# schematic.net
KiCad netlist of a schematic drawn in Altium Designer
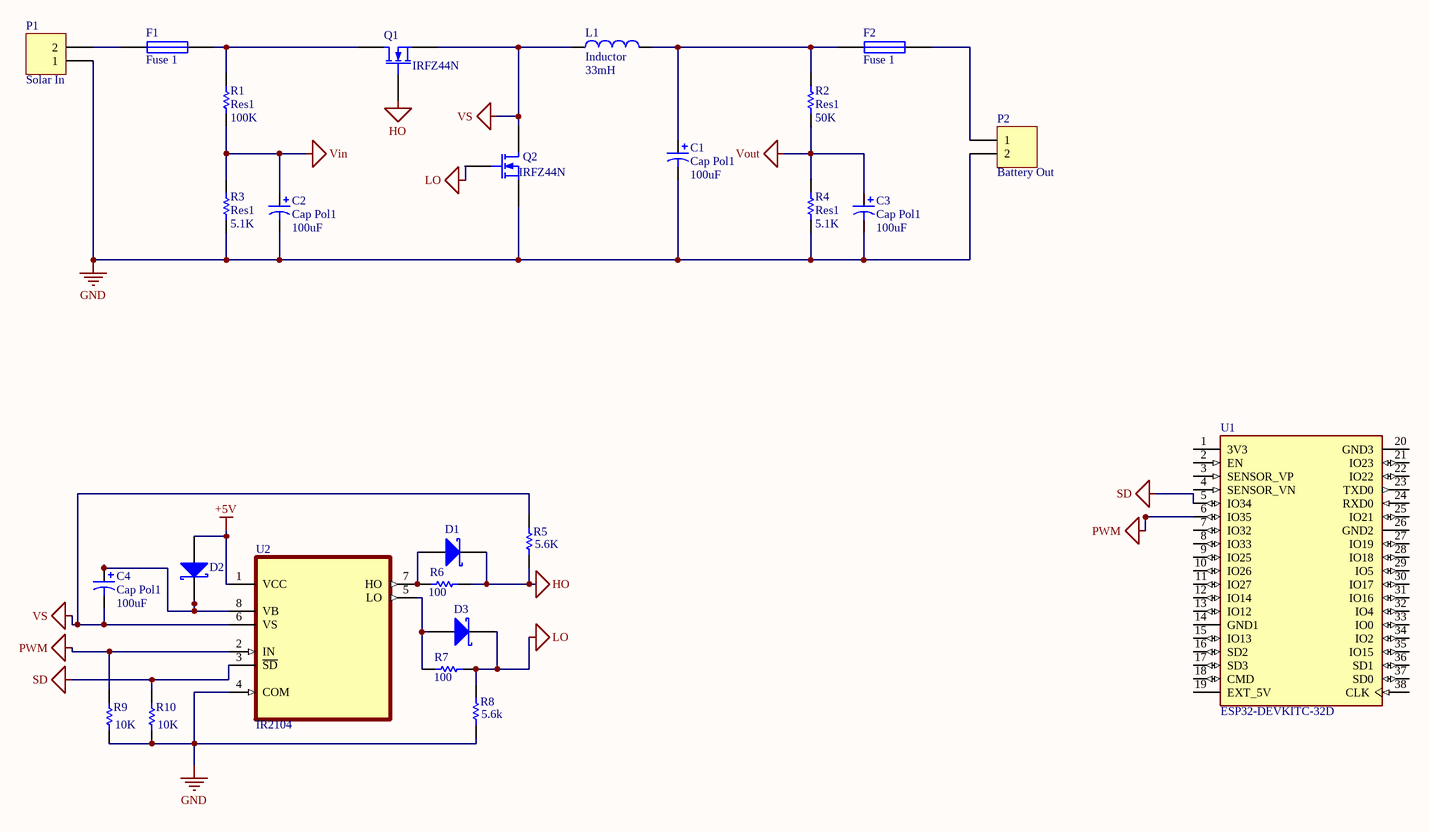
[diagram p0: schematic.SchDoc]

(export (version "E")
  (design (tool "Eeschema 10.0.6"))
  (components
    (comp (ref "C1")
      (value "Cap Pol1")
      (footprint "RB7.6-15")
      (description "Polarized Capacitor (Radial)")
      (fields (field (name "ALTIUM_VALUE") "100uF") (field (name "PUBLISHER") "Altium Limited"))
      (libsource (lib "Miscellaneous Devices") (part "Cap Pol1"))
    )
    (comp (ref "C2")
      (value "Cap Pol1")
      (footprint "RB7.6-15")
      (description "Polarized Capacitor (Radial)")
      (fields (field (name "ALTIUM_VALUE") "100uF") (field (name "PUBLISHER") "Altium Limited"))
      (libsource (lib "Miscellaneous Devices") (part "Cap Pol1"))
    )
    (comp (ref "C3")
      (value "Cap Pol1")
      (footprint "RB7.6-15")
      (description "Polarized Capacitor (Radial)")
      (fields (field (name "ALTIUM_VALUE") "100uF") (field (name "PUBLISHER") "Altium Limited"))
      (libsource (lib "Miscellaneous Devices") (part "Cap Pol1"))
    )
    (comp (ref "C4")
      (value "Cap Pol1")
      (footprint "RB7.6-15")
      (description "Polarized Capacitor (Radial)")
      (fields (field (name "ALTIUM_VALUE") "100uF") (field (name "PUBLISHER") "Altium Limited"))
      (libsource (lib "Miscellaneous Devices") (part "Cap Pol1"))
    )
    (comp (ref "D1")
      (value "Diode 10TQ035")
      (footprint "TO-220AC")
      (description "Schottky Rectifier")
      (fields (field (name "PUBLISHER") "Altium Limited"))
      (libsource (lib "Miscellaneous Devices") (part "Diode 10TQ035"))
    )
    (comp (ref "D2")
      (value "Diode 10TQ035")
      (footprint "TO-220AC")
      (description "Schottky Rectifier")
      (fields (field (name "PUBLISHER") "Altium Limited"))
      (libsource (lib "Miscellaneous Devices") (part "Diode 10TQ035"))
    )
    (comp (ref "D3")
      (value "Diode 10TQ035")
      (footprint "TO-220AC")
      (description "Schottky Rectifier")
      (fields (field (name "PUBLISHER") "Altium Limited"))
      (libsource (lib "Miscellaneous Devices") (part "Diode 10TQ035"))
    )
    (comp (ref "F1")
      (value "Fuse 1")
      (footprint "PIN-W2/E2.8")
      (description "Fuse")
      (fields (field (name "PUBLISHER") "Altium Limited"))
      (libsource (lib "Miscellaneous Devices") (part "Fuse 1"))
    )
    (comp (ref "F2")
      (value "Fuse 1")
      (footprint "PIN-W2/E2.8")
      (description "Fuse")
      (fields (field (name "PUBLISHER") "Altium Limited"))
      (libsource (lib "Miscellaneous Devices") (part "Fuse 1"))
    )
    (comp (ref "L1")
      (value "Inductor")
      (footprint "0402-A")
      (fields (field (name "ALTIUM_VALUE") "33mH") (field (name "PUBLISHER") "Altium Limited"))
      (libsource (lib "Miscellaneous Devices") (part "Inductor"))
    )
    (comp (ref "P1")
      (value "Solar In")
      (footprint "HDR1X2")
      (description "Header, 2-Pin")
      (fields (field (name "PUBLISHER") "Altium Limited"))
      (libsource (lib "Miscellaneous Connectors") (part "Header 2"))
    )
    (comp (ref "P2")
      (value "Battery Out")
      (footprint "HDR1X2")
      (description "Header, 2-Pin")
      (fields (field (name "PUBLISHER") "Altium Limited"))
      (libsource (lib "") (part "Header 2_1"))
    )
    (comp (ref "Q1")
      (value "IRFZ44N")
      (footprint "E3")
      (description "N-Channel MOSFET")
      (fields (field (name "PUBLISHER") "Altium Limited"))
      (libsource (lib "Miscellaneous Devices") (part "MOSFET-N"))
    )
    (comp (ref "Q2")
      (value "IRFZ44N")
      (footprint "E3")
      (description "N-Channel MOSFET")
      (fields (field (name "PUBLISHER") "Altium Limited"))
      (libsource (lib "Miscellaneous Devices") (part "MOSFET-N"))
    )
    (comp (ref "R1")
      (value "Res1")
      (footprint "AXIAL-0.3")
      (description "Resistor")
      (fields (field (name "ALTIUM_VALUE") "100K") (field (name "PUBLISHER") "Altium Limited"))
      (libsource (lib "Miscellaneous Devices") (part "Res1"))
    )
    (comp (ref "R2")
      (value "Res1")
      (footprint "AXIAL-0.3")
      (description "Resistor")
      (fields (field (name "ALTIUM_VALUE") "50K") (field (name "PUBLISHER") "Altium Limited"))
      (libsource (lib "Miscellaneous Devices") (part "Res1"))
    )
    (comp (ref "R3")
      (value "Res1")
      (footprint "AXIAL-0.3")
      (description "Resistor")
      (fields (field (name "ALTIUM_VALUE") "5.1K") (field (name "PUBLISHER") "Altium Limited"))
      (libsource (lib "Miscellaneous Devices") (part "Res1"))
    )
    (comp (ref "R4")
      (value "Res1")
      (footprint "AXIAL-0.3")
      (description "Resistor")
      (fields (field (name "ALTIUM_VALUE") "5.1K") (field (name "PUBLISHER") "Altium Limited"))
      (libsource (lib "Miscellaneous Devices") (part "Res1"))
    )
    (comp (ref "R5")
      (value "5.6K")
      (footprint "AXIAL-0.3")
      (description "Resistor")
      (fields (field (name "Comment") "Res1") (field (name "PUBLISHER") "Altium Limited"))
      (libsource (lib "Miscellaneous Devices") (part "Res1"))
    )
    (comp (ref "R6")
      (value "100")
      (footprint "AXIAL-0.3")
      (description "Resistor")
      (fields (field (name "Comment") "Res1") (field (name "PUBLISHER") "Altium Limited"))
      (libsource (lib "Miscellaneous Devices") (part "Res1"))
    )
    (comp (ref "R7")
      (value "100")
      (footprint "AXIAL-0.3")
      (description "Resistor")
      (fields (field (name "Comment") "Res1") (field (name "PUBLISHER") "Altium Limited"))
      (libsource (lib "Miscellaneous Devices") (part "Res1"))
    )
    (comp (ref "R8")
      (value "5.6k")
      (footprint "AXIAL-0.3")
      (description "Resistor")
      (fields (field (name "Comment") "Res1") (field (name "PUBLISHER") "Altium Limited"))
      (libsource (lib "Miscellaneous Devices") (part "Res1"))
    )
    (comp (ref "R9")
      (value "10K")
      (footprint "AXIAL-0.3")
      (description "Resistor")
      (fields (field (name "Comment") "Res1") (field (name "PUBLISHER") "Altium Limited"))
      (libsource (lib "Miscellaneous Devices") (part "Res1"))
    )
    (comp (ref "R10")
      (value "10K")
      (footprint "AXIAL-0.3")
      (description "Resistor")
      (fields (field (name "Comment") "Res1") (field (name "PUBLISHER") "Altium Limited"))
      (libsource (lib "Miscellaneous Devices") (part "Res1"))
    )
    (comp (ref "U1")
      (value "ESP32-DEVKITC-32D")
      (footprint "MODULE_ESP32-DEVKITC-32D")
      (description "Eval Board For Esp-Wroom-32")
      (libsource (lib "ESP32-DEVKITC-32D") (part "ESP32-DEVKITC-32D"))
    )
    (comp (ref "U2")
      (value "IR2104")
      (footprint "DIP254P762X533-8")
      (description "Half-Bridge Gate Driver IC Non-Inverting 8-PDIP")
      (fields (field (name "MF") "Infineon Technologies"))
      (libsource (lib "IR2104") (part "IR2104"))
    )
  )
  (nets
    (net (code "1") (name "+5V") (class "Default")
      (node (ref "D2") (pin "3") (pinfunction "A_3") (pintype "passive"))
      (node (ref "U2") (pin "1") (pinfunction "VCC_1") (pintype "power_in"))
    )
    (net (code "2") (name "GND") (class "Default")
      (node (ref "C1") (pin "2") (pinfunction "2_2") (pintype "passive"))
      (node (ref "C2") (pin "2") (pinfunction "2_2") (pintype "passive"))
      (node (ref "C3") (pin "2") (pinfunction "2_2") (pintype "passive"))
      (node (ref "P1") (pin "1") (pinfunction "1_1") (pintype "passive"))
      (node (ref "P2") (pin "2") (pinfunction "2_2") (pintype "passive"))
      (node (ref "Q2") (pin "3") (pinfunction "S_3") (pintype "passive"))
      (node (ref "R10") (pin "1") (pinfunction "1_1") (pintype "passive"))
      (node (ref "R3") (pin "1") (pinfunction "1_1") (pintype "passive"))
      (node (ref "R4") (pin "1") (pinfunction "1_1") (pintype "passive"))
      (node (ref "R8") (pin "1") (pinfunction "1_1") (pintype "passive"))
      (node (ref "R9") (pin "1") (pinfunction "1_1") (pintype "passive"))
      (node (ref "U2") (pin "4") (pinfunction "COM_4") (pintype "input"))
    )
    (net (code "3") (name "HO") (class "Default")
      (node (ref "D1") (pin "1") (pinfunction "K_1") (pintype "passive"))
      (node (ref "Q1") (pin "2") (pinfunction "G_2") (pintype "passive"))
      (node (ref "R5") (pin "1") (pinfunction "1_1") (pintype "passive"))
      (node (ref "R6") (pin "1") (pinfunction "1_1") (pintype "passive"))
    )
    (net (code "4") (name "LO") (class "Default")
      (node (ref "D3") (pin "1") (pinfunction "K_1") (pintype "passive"))
      (node (ref "Q2") (pin "2") (pinfunction "G_2") (pintype "passive"))
      (node (ref "R7") (pin "1") (pinfunction "1_1") (pintype "passive"))
      (node (ref "R8") (pin "2") (pinfunction "2_2") (pintype "passive"))
    )
    (net (code "5") (name "Net-(C1-Pad1)") (class "Default")
      (node (ref "C1") (pin "1") (pinfunction "1_1") (pintype "passive"))
      (node (ref "F2") (pin "1") (pinfunction "1_1") (pintype "passive"))
      (node (ref "L1") (pin "2") (pinfunction "2_2") (pintype "passive"))
      (node (ref "R2") (pin "2") (pinfunction "2_2") (pintype "passive"))
    )
    (net (code "6") (name "Net-(D1-A)") (class "Default")
      (node (ref "D1") (pin "3") (pinfunction "A_3") (pintype "passive"))
      (node (ref "R6") (pin "2") (pinfunction "2_2") (pintype "passive"))
      (node (ref "U2") (pin "7") (pinfunction "HO_7") (pintype "output"))
    )
    (net (code "7") (name "Net-(D2-K)") (class "Default")
      (node (ref "C4") (pin "1") (pinfunction "1_1") (pintype "passive"))
      (node (ref "D2") (pin "1") (pinfunction "K_1") (pintype "passive"))
      (node (ref "U2") (pin "8") (pinfunction "VB_8") (pintype "power_in"))
    )
    (net (code "8") (name "Net-(D3-A)") (class "Default")
      (node (ref "D3") (pin "3") (pinfunction "A_3") (pintype "passive"))
      (node (ref "R7") (pin "2") (pinfunction "2_2") (pintype "passive"))
      (node (ref "U2") (pin "5") (pinfunction "LO_5") (pintype "output"))
    )
    (net (code "9") (name "Net-(F1-Pad1)") (class "Default")
      (node (ref "F1") (pin "1") (pinfunction "1_1") (pintype "passive"))
      (node (ref "P1") (pin "2") (pinfunction "2_2") (pintype "passive"))
    )
    (net (code "10") (name "Net-(F2-Pad2)") (class "Default")
      (node (ref "F2") (pin "2") (pinfunction "2_2") (pintype "passive"))
      (node (ref "P2") (pin "1") (pinfunction "1_1") (pintype "passive"))
    )
    (net (code "11") (name "Net-(Q1-D)") (class "Default")
      (node (ref "F1") (pin "2") (pinfunction "2_2") (pintype "passive"))
      (node (ref "Q1") (pin "1") (pinfunction "D_1") (pintype "passive"))
      (node (ref "R1") (pin "2") (pinfunction "2_2") (pintype "passive"))
    )
    (net (code "12") (name "PWM") (class "Default")
      (node (ref "R9") (pin "2") (pinfunction "2_2") (pintype "passive"))
      (node (ref "U1") (pin "6") (pinfunction "IO35_6") (pintype "bidirectional"))
      (node (ref "U2") (pin "2") (pinfunction "IN_2") (pintype "input"))
    )
    (net (code "13") (name "SD") (class "Default")
      (node (ref "R10") (pin "2") (pinfunction "2_2") (pintype "passive"))
      (node (ref "U1") (pin "5") (pinfunction "IO34_5") (pintype "bidirectional"))
      (node (ref "U2") (pin "3") (pinfunction "~{SD}_3") (pintype "passive"))
    )
    (net (code "14") (name "VS") (class "Default")
      (node (ref "C4") (pin "2") (pinfunction "2_2") (pintype "passive"))
      (node (ref "L1") (pin "1") (pinfunction "1_1") (pintype "passive"))
      (node (ref "Q1") (pin "3") (pinfunction "S_3") (pintype "passive"))
      (node (ref "Q2") (pin "1") (pinfunction "D_1") (pintype "passive"))
      (node (ref "R5") (pin "2") (pinfunction "2_2") (pintype "passive"))
      (node (ref "U2") (pin "6") (pinfunction "VS_6") (pintype "power_in"))
    )
    (net (code "15") (name "Vin") (class "Default")
      (node (ref "C2") (pin "1") (pinfunction "1_1") (pintype "passive"))
      (node (ref "R1") (pin "1") (pinfunction "1_1") (pintype "passive"))
      (node (ref "R3") (pin "2") (pinfunction "2_2") (pintype "passive"))
    )
    (net (code "16") (name "Vout") (class "Default")
      (node (ref "C3") (pin "1") (pinfunction "1_1") (pintype "passive"))
      (node (ref "R2") (pin "1") (pinfunction "1_1") (pintype "passive"))
      (node (ref "R4") (pin "2") (pinfunction "2_2") (pintype "passive"))
    )
    (net (code "17") (name "unconnected-(U1-3V3-Pad1)") (class "Default")
      (node (ref "U1") (pin "1") (pinfunction "3V3_1") (pintype "power_in"))
    )
    (net (code "18") (name "unconnected-(U1-CLK-Pad38)") (class "Default")
      (node (ref "U1") (pin "38") (pinfunction "CLK_38") (pintype "input"))
    )
    (net (code "19") (name "unconnected-(U1-CMD-Pad18)") (class "Default")
      (node (ref "U1") (pin "18") (pinfunction "CMD_18") (pintype "bidirectional"))
    )
    (net (code "20") (name "unconnected-(U1-EN-Pad2)") (class "Default")
      (node (ref "U1") (pin "2") (pinfunction "EN_2") (pintype "input"))
    )
    (net (code "21") (name "unconnected-(U1-EXT_5V-Pad19)") (class "Default")
      (node (ref "U1") (pin "19") (pinfunction "EXT_5V_19") (pintype "power_in"))
    )
    (net (code "22") (name "unconnected-(U1-GND1-Pad14)") (class "Default")
      (node (ref "U1") (pin "14") (pinfunction "GND1_14") (pintype "power_in"))
    )
    (net (code "23") (name "unconnected-(U1-GND2-Pad26)") (class "Default")
      (node (ref "U1") (pin "26") (pinfunction "GND2_26") (pintype "power_in"))
    )
    (net (code "24") (name "unconnected-(U1-GND3-Pad20)") (class "Default")
      (node (ref "U1") (pin "20") (pinfunction "GND3_20") (pintype "power_in"))
    )
    (net (code "25") (name "unconnected-(U1-IO0-Pad33)") (class "Default")
      (node (ref "U1") (pin "33") (pinfunction "IO0_33") (pintype "bidirectional"))
    )
    (net (code "26") (name "unconnected-(U1-IO2-Pad34)") (class "Default")
      (node (ref "U1") (pin "34") (pinfunction "IO2_34") (pintype "bidirectional"))
    )
    (net (code "27") (name "unconnected-(U1-IO4-Pad32)") (class "Default")
      (node (ref "U1") (pin "32") (pinfunction "IO4_32") (pintype "bidirectional"))
    )
    (net (code "28") (name "unconnected-(U1-IO5-Pad29)") (class "Default")
      (node (ref "U1") (pin "29") (pinfunction "IO5_29") (pintype "bidirectional"))
    )
    (net (code "29") (name "unconnected-(U1-IO12-Pad13)") (class "Default")
      (node (ref "U1") (pin "13") (pinfunction "IO12_13") (pintype "bidirectional"))
    )
    (net (code "30") (name "unconnected-(U1-IO13-Pad15)") (class "Default")
      (node (ref "U1") (pin "15") (pinfunction "IO13_15") (pintype "bidirectional"))
    )
    (net (code "31") (name "unconnected-(U1-IO14-Pad12)") (class "Default")
      (node (ref "U1") (pin "12") (pinfunction "IO14_12") (pintype "bidirectional"))
    )
    (net (code "32") (name "unconnected-(U1-IO15-Pad35)") (class "Default")
      (node (ref "U1") (pin "35") (pinfunction "IO15_35") (pintype "bidirectional"))
    )
    (net (code "33") (name "unconnected-(U1-IO16-Pad31)") (class "Default")
      (node (ref "U1") (pin "31") (pinfunction "IO16_31") (pintype "bidirectional"))
    )
    (net (code "34") (name "unconnected-(U1-IO17-Pad30)") (class "Default")
      (node (ref "U1") (pin "30") (pinfunction "IO17_30") (pintype "bidirectional"))
    )
    (net (code "35") (name "unconnected-(U1-IO18-Pad28)") (class "Default")
      (node (ref "U1") (pin "28") (pinfunction "IO18_28") (pintype "bidirectional"))
    )
    (net (code "36") (name "unconnected-(U1-IO19-Pad27)") (class "Default")
      (node (ref "U1") (pin "27") (pinfunction "IO19_27") (pintype "bidirectional"))
    )
    (net (code "37") (name "unconnected-(U1-IO21-Pad25)") (class "Default")
      (node (ref "U1") (pin "25") (pinfunction "IO21_25") (pintype "bidirectional"))
    )
    (net (code "38") (name "unconnected-(U1-IO22-Pad22)") (class "Default")
      (node (ref "U1") (pin "22") (pinfunction "IO22_22") (pintype "bidirectional"))
    )
    (net (code "39") (name "unconnected-(U1-IO23-Pad21)") (class "Default")
      (node (ref "U1") (pin "21") (pinfunction "IO23_21") (pintype "bidirectional"))
    )
    (net (code "40") (name "unconnected-(U1-IO25-Pad9)") (class "Default")
      (node (ref "U1") (pin "9") (pinfunction "IO25_9") (pintype "bidirectional"))
    )
    (net (code "41") (name "unconnected-(U1-IO26-Pad10)") (class "Default")
      (node (ref "U1") (pin "10") (pinfunction "IO26_10") (pintype "bidirectional"))
    )
    (net (code "42") (name "unconnected-(U1-IO27-Pad11)") (class "Default")
      (node (ref "U1") (pin "11") (pinfunction "IO27_11") (pintype "bidirectional"))
    )
    (net (code "43") (name "unconnected-(U1-IO32-Pad7)") (class "Default")
      (node (ref "U1") (pin "7") (pinfunction "IO32_7") (pintype "bidirectional"))
    )
    (net (code "44") (name "unconnected-(U1-IO33-Pad8)") (class "Default")
      (node (ref "U1") (pin "8") (pinfunction "IO33_8") (pintype "bidirectional"))
    )
    (net (code "45") (name "unconnected-(U1-RXD0-Pad24)") (class "Default")
      (node (ref "U1") (pin "24") (pinfunction "RXD0_24") (pintype "input"))
    )
    (net (code "46") (name "unconnected-(U1-SD0-Pad37)") (class "Default")
      (node (ref "U1") (pin "37") (pinfunction "SD0_37") (pintype "bidirectional"))
    )
    (net (code "47") (name "unconnected-(U1-SD1-Pad36)") (class "Default")
      (node (ref "U1") (pin "36") (pinfunction "SD1_36") (pintype "bidirectional"))
    )
    (net (code "48") (name "unconnected-(U1-SD2-Pad16)") (class "Default")
      (node (ref "U1") (pin "16") (pinfunction "SD2_16") (pintype "bidirectional"))
    )
    (net (code "49") (name "unconnected-(U1-SD3-Pad17)") (class "Default")
      (node (ref "U1") (pin "17") (pinfunction "SD3_17") (pintype "bidirectional"))
    )
    (net (code "50") (name "unconnected-(U1-SENSOR_VN-Pad4)") (class "Default")
      (node (ref "U1") (pin "4") (pinfunction "SENSOR_VN_4") (pintype "input"))
    )
    (net (code "51") (name "unconnected-(U1-SENSOR_VP-Pad3)") (class "Default")
      (node (ref "U1") (pin "3") (pinfunction "SENSOR_VP_3") (pintype "input"))
    )
    (net (code "52") (name "unconnected-(U1-TXD0-Pad23)") (class "Default")
      (node (ref "U1") (pin "23") (pinfunction "TXD0_23") (pintype "output"))
    )
  )
)
